# Microcontrolador.net
KiCad netlist of a schematic drawn in Altium Designer
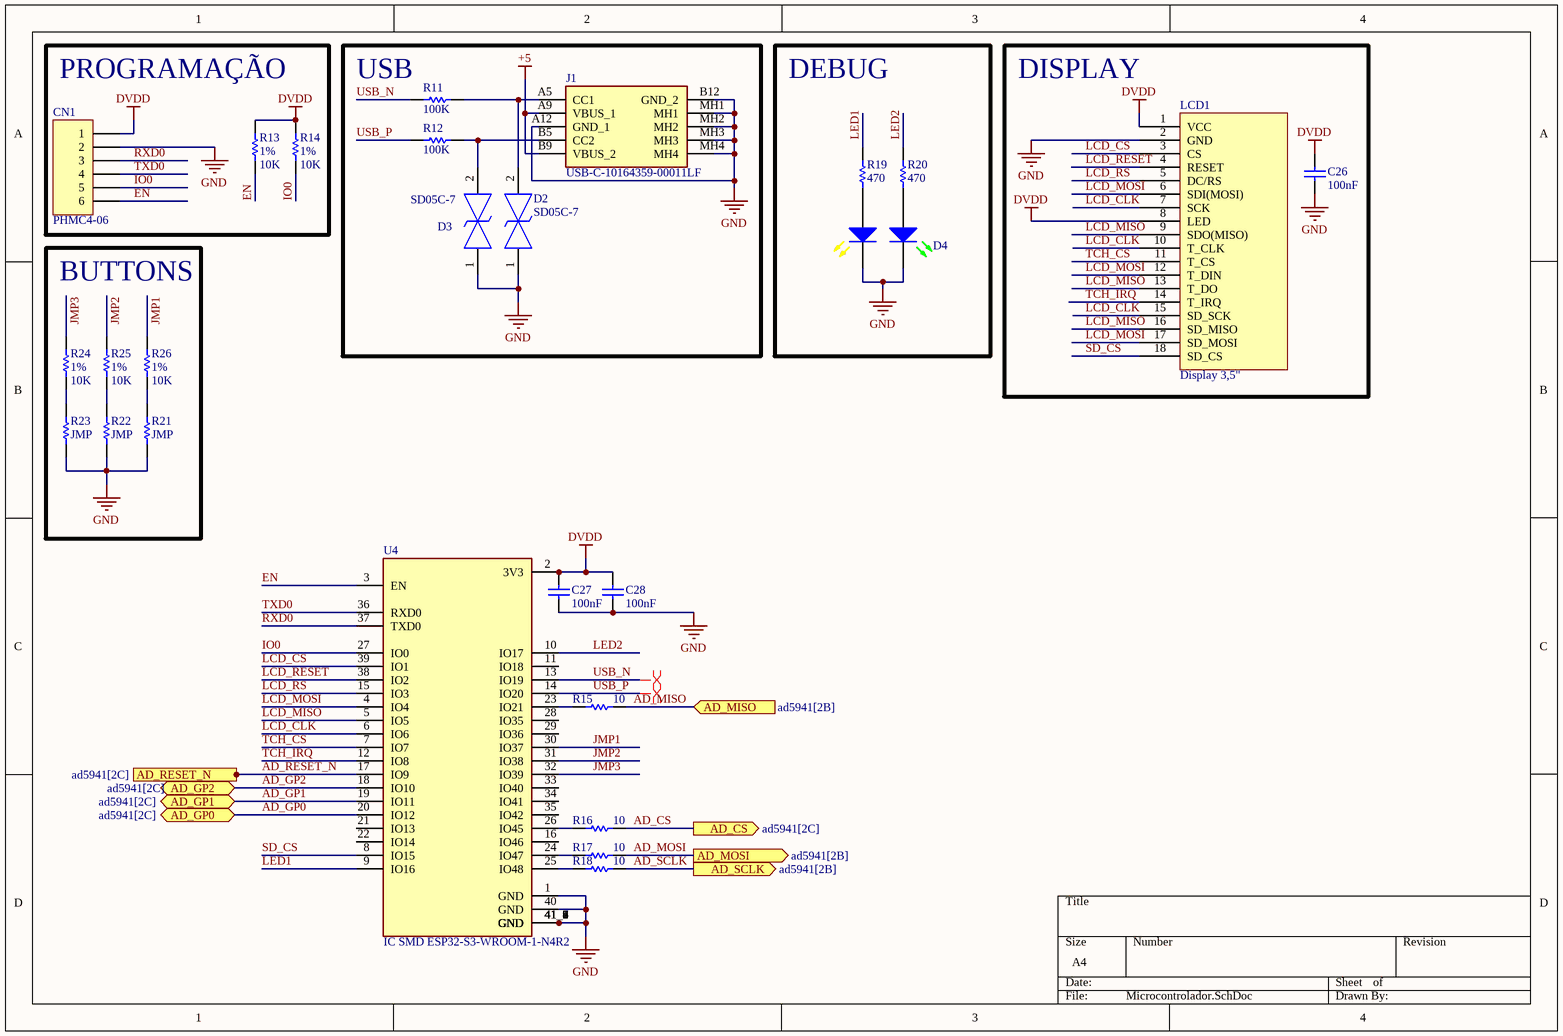
[diagram p0: Microcontrolador.SchDoc]

(export (version "E")
  (design (tool "Eeschema 10.0.6"))
  (components
    (comp (ref "C26")
      (value "100nF")
      (footprint "CAP0805OK")
      (fields
        (field (name "TOLERANCE") "10%")
        (field (name "VOLTAGE") "25V")
        (field (name "Comment") "CAP SMD CER 100NF 25V 0805")
      )
      (libsource (lib "BIB SCH GERAL") (part "CAP SMD CER 100NF 25V 0805"))
    )
    (comp (ref "C27")
      (value "100nF")
      (footprint "CAP0805OK")
      (fields
        (field (name "TOLERANCE") "10%")
        (field (name "VOLTAGE") "25V")
        (field (name "Comment") "CAP SMD CER 100NF 25V 0805")
      )
      (libsource (lib "BIB SCH GERAL") (part "CAP SMD CER 100NF 25V 0805"))
    )
    (comp (ref "C28")
      (value "100nF")
      (footprint "CAP0805OK")
      (fields
        (field (name "TOLERANCE") "10%")
        (field (name "VOLTAGE") "25V")
        (field (name "Comment") "CAP SMD CER 100NF 25V 0805")
      )
      (libsource (lib "BIB SCH GERAL") (part "CAP SMD CER 100NF 25V 0805"))
    )
    (comp (ref "CN1")
      (value "CN MAC 6 VIAS 180º 2.54MM")
      (footprint "PHMC4-06")
      (description "gravação micro")
      (fields (field (name "MANUFACTURER") "METALTEX") (field (name "MANUFACTURER PART NUMBER") "PHMC4-06"))
      (libsource (lib "BIB SCH GERAL") (part "CN MAC 6 VIAS 180º 2.54MM"))
    )
    (comp (ref "D2")
      (value "SD05C-7")
      (footprint "SOD2513X120N")
      (description "TVS Diode (Bi-directional)")
      (fields (field (name "MOUSER PART NUMBER") "621-SD05C-7"))
      (libsource (lib "BIB SCH GERAL") (part "SD05C-7"))
    )
    (comp (ref "D3")
      (value "SD05C-7")
      (footprint "SOD2513X120N")
      (description "TVS Diode (Bi-directional)")
      (fields (field (name "MOUSER PART NUMBER") "621-SD05C-7"))
      (libsource (lib "BIB SCH GERAL") (part "SD05C-7"))
    )
    (comp (ref "D4")
      (value "LED SMD DUAL")
      (footprint "LTST-C197")
      (libsource (lib "BIB SCH GERAL") (part "LED SMD DUAL"))
    )
    (comp (ref "J1")
      (value "USB-C-10164359-00011LF")
      (footprint "LIB_GERAL_V2:USB-C-1016435900011LF")
      (description "Connector")
      (fields
        (field (name "MANUFACTURER_PART_NUMBER") "10164359-00011LF")
        (field (name "MOUSER PART NUMBER") "649-10164359-00011LF")
      )
      (libsource (lib "BIB SCH GERAL") (part "USB-C-10164359-00011LF"))
    )
    (comp (ref "LCD1")
      (value "Display 3,5\"")
      (footprint "Display_3.5\"_SPI_480X320")
      (description "Display TFT SPI 480X320")
      (libsource (lib "BIB SCH GERAL") (part "Display 3,5{dblquote} SPI"))
    )
    (comp (ref "R11")
      (value "100K")
      (footprint "res0805ok")
      (fields (field (name "TOLERANCE") "1%") (field (name "Comment") "RES SMD 100K 1% 0805"))
      (libsource (lib "BIB SCH GERAL") (part "RES SMD 10K 1% 0805"))
    )
    (comp (ref "R12")
      (value "100K")
      (footprint "res0805ok")
      (fields (field (name "TOLERANCE") "1%") (field (name "Comment") "RES SMD 100K 1% 0805"))
      (libsource (lib "BIB SCH GERAL") (part "RES SMD 10K 1% 0805"))
    )
    (comp (ref "R13")
      (value "10K")
      (footprint "res0805ok")
      (fields (field (name "TOLERANCE") "1%") (field (name "Comment") "RES SMD 10K 1% 0805"))
      (libsource (lib "BIB SCH GERAL") (part "RES SMD 10K 1% 0805"))
    )
    (comp (ref "R14")
      (value "10K")
      (footprint "res0805ok")
      (fields (field (name "TOLERANCE") "1%") (field (name "Comment") "RES SMD 10K 1% 0805"))
      (libsource (lib "BIB SCH GERAL") (part "RES SMD 10K 1% 0805"))
    )
    (comp (ref "R15")
      (value "10")
      (footprint "res0805ok")
      (fields (field (name "TOLERANCE") "1%") (field (name "Comment") "RES SMD 10 1% 0805"))
      (libsource (lib "BIB SCH GERAL") (part "RES SMD 10K 1% 0805"))
    )
    (comp (ref "R16")
      (value "10")
      (footprint "res0805ok")
      (fields (field (name "TOLERANCE") "1%") (field (name "Comment") "RES SMD 10 1% 0805"))
      (libsource (lib "BIB SCH GERAL") (part "RES SMD 10K 1% 0805"))
    )
    (comp (ref "R17")
      (value "10")
      (footprint "res0805ok")
      (fields (field (name "TOLERANCE") "1%") (field (name "Comment") "RES SMD 10 1% 0805"))
      (libsource (lib "BIB SCH GERAL") (part "RES SMD 10K 1% 0805"))
    )
    (comp (ref "R18")
      (value "10")
      (footprint "res0805ok")
      (fields (field (name "TOLERANCE") "1%") (field (name "Comment") "RES SMD 10 1% 0805"))
      (libsource (lib "BIB SCH GERAL") (part "RES SMD 10K 1% 0805"))
    )
    (comp (ref "R19")
      (value "470")
      (footprint "res0805ok")
      (fields (field (name "TOLERANCE") "1%") (field (name "Comment") "RES SMD 1K 1% 0805"))
      (libsource (lib "BIB SCH GERAL") (part "RES SMD 1K 1% 0805"))
    )
    (comp (ref "R20")
      (value "470")
      (footprint "res0805ok")
      (fields (field (name "TOLERANCE") "1%") (field (name "Comment") "RES SMD 1K 1% 0805"))
      (libsource (lib "BIB SCH GERAL") (part "RES SMD 1K 1% 0805"))
    )
    (comp (ref "R21")
      (value "JMP")
      (footprint "JMP0805")
      (fields (field (name "TOLERANCE") "1%") (field (name "Comment") "RES SMD 10K 1% 0805"))
      (libsource (lib "BIB SCH GERAL") (part "RES SMD 10K 1% 0805"))
    )
    (comp (ref "R22")
      (value "JMP")
      (footprint "JMP0805")
      (fields (field (name "TOLERANCE") "1%") (field (name "Comment") "RES SMD 10K 1% 0805"))
      (libsource (lib "BIB SCH GERAL") (part "RES SMD 10K 1% 0805"))
    )
    (comp (ref "R23")
      (value "JMP")
      (footprint "JMP0805")
      (fields (field (name "TOLERANCE") "1%") (field (name "Comment") "RES SMD 10K 1% 0805"))
      (libsource (lib "BIB SCH GERAL") (part "RES SMD 10K 1% 0805"))
    )
    (comp (ref "R24")
      (value "10K")
      (footprint "res0805ok")
      (fields (field (name "TOLERANCE") "1%") (field (name "Comment") "RES SMD 10K 1% 0805"))
      (libsource (lib "BIB SCH GERAL") (part "RES SMD 10K 1% 0805"))
    )
    (comp (ref "R25")
      (value "10K")
      (footprint "res0805ok")
      (fields (field (name "TOLERANCE") "1%") (field (name "Comment") "RES SMD 10K 1% 0805"))
      (libsource (lib "BIB SCH GERAL") (part "RES SMD 10K 1% 0805"))
    )
    (comp (ref "R26")
      (value "10K")
      (footprint "res0805ok")
      (fields (field (name "TOLERANCE") "1%") (field (name "Comment") "RES SMD 10K 1% 0805"))
      (libsource (lib "BIB SCH GERAL") (part "RES SMD 10K 1% 0805"))
    )
    (comp (ref "U4")
      (value "IC SMD ESP32-S3-WROOM-1-N4R2")
      (footprint "XCVR_ESP32-S3-WROOM-1-N4R2")
      (description "Bluetooth, WiFi 802.11b/g/n, Bluetooth v5.0 Transceiver Module 2.4GHz PCB Trace Surface Mount")
      (fields (field (name "MF") "Espressif Systems") (field (name "MP") "ESP32-S3-WROOM-1-N4R2"))
      (libsource (lib "BIB SCH GERAL") (part "IC SMD ESP32-S3-WROOM-1-N4R2"))
    )
  )
  (nets
    (net (code "1") (name "+5") (class "Default")
      (node (ref "J1") (pin "A9") (pinfunction "VBUS_1_A9") (pintype "passive"))
      (node (ref "J1") (pin "B9") (pinfunction "VBUS_2_B9") (pintype "passive"))
    )
    (net (code "2") (name "/AD_CS") (class "Default")
      (node (ref "R16") (pin "1") (pinfunction "1_1") (pintype "passive"))
    )
    (net (code "3") (name "/AD_GP0") (class "Default")
      (node (ref "U4") (pin "20") (pinfunction "IO12_20") (pintype "passive"))
    )
    (net (code "4") (name "/AD_GP1") (class "Default")
      (node (ref "U4") (pin "19") (pinfunction "IO11_19") (pintype "passive"))
    )
    (net (code "5") (name "/AD_GP2") (class "Default")
      (node (ref "U4") (pin "18") (pinfunction "IO10_18") (pintype "passive"))
    )
    (net (code "6") (name "/AD_MISO") (class "Default")
      (node (ref "R15") (pin "1") (pinfunction "1_1") (pintype "passive"))
    )
    (net (code "7") (name "/AD_MOSI") (class "Default")
      (node (ref "R17") (pin "1") (pinfunction "1_1") (pintype "passive"))
    )
    (net (code "8") (name "/AD_RESET_N") (class "Default")
      (node (ref "U4") (pin "17") (pinfunction "IO9_17") (pintype "passive"))
    )
    (net (code "9") (name "/AD_SCLK") (class "Default")
      (node (ref "R18") (pin "1") (pinfunction "1_1") (pintype "passive"))
    )
    (net (code "10") (name "/EN") (class "Default")
      (node (ref "CN1") (pin "6") (pinfunction "6_6") (pintype "passive"))
      (node (ref "R13") (pin "1") (pinfunction "1_1") (pintype "passive"))
      (node (ref "U4") (pin "3") (pinfunction "EN_3") (pintype "passive"))
    )
    (net (code "11") (name "/IO0") (class "Default")
      (node (ref "CN1") (pin "5") (pinfunction "5_5") (pintype "passive"))
      (node (ref "R14") (pin "1") (pinfunction "1_1") (pintype "passive"))
      (node (ref "U4") (pin "27") (pinfunction "IO0_27") (pintype "passive"))
    )
    (net (code "12") (name "/JMP1") (class "Default")
      (node (ref "R26") (pin "2") (pinfunction "2_2") (pintype "passive"))
      (node (ref "U4") (pin "30") (pinfunction "IO37_30") (pintype "passive"))
    )
    (net (code "13") (name "/JMP2") (class "Default")
      (node (ref "R25") (pin "2") (pinfunction "2_2") (pintype "passive"))
      (node (ref "U4") (pin "31") (pinfunction "IO38_31") (pintype "passive"))
    )
    (net (code "14") (name "/JMP3") (class "Default")
      (node (ref "R24") (pin "2") (pinfunction "2_2") (pintype "passive"))
      (node (ref "U4") (pin "32") (pinfunction "IO39_32") (pintype "passive"))
    )
    (net (code "15") (name "/LCD_CLK") (class "Default")
      (node (ref "LCD1") (pin "10") (pinfunction "T_CLK_10") (pintype "passive"))
      (node (ref "LCD1") (pin "15") (pinfunction "SD_SCK_15") (pintype "passive"))
      (node (ref "LCD1") (pin "7") (pinfunction "SCK_7") (pintype "passive"))
      (node (ref "U4") (pin "6") (pinfunction "IO6_6") (pintype "passive"))
    )
    (net (code "16") (name "/LCD_CS") (class "Default")
      (node (ref "LCD1") (pin "3") (pinfunction "CS_3") (pintype "passive"))
      (node (ref "U4") (pin "39") (pinfunction "IO1_39") (pintype "passive"))
    )
    (net (code "17") (name "/LCD_MISO") (class "Default")
      (node (ref "LCD1") (pin "13") (pinfunction "T_DO_13") (pintype "passive"))
      (node (ref "LCD1") (pin "16") (pinfunction "SD_MISO_16") (pintype "passive"))
      (node (ref "LCD1") (pin "9") (pinfunction "SDO(MISO)_9") (pintype "passive"))
      (node (ref "U4") (pin "5") (pinfunction "IO5_5") (pintype "passive"))
    )
    (net (code "18") (name "/LCD_MOSI") (class "Default")
      (node (ref "LCD1") (pin "12") (pinfunction "T_DIN_12") (pintype "passive"))
      (node (ref "LCD1") (pin "17") (pinfunction "SD_MOSI_17") (pintype "passive"))
      (node (ref "LCD1") (pin "6") (pinfunction "SDI(MOSI)_6") (pintype "passive"))
      (node (ref "U4") (pin "4") (pinfunction "IO4_4") (pintype "passive"))
    )
    (net (code "19") (name "/LCD_RESET") (class "Default")
      (node (ref "LCD1") (pin "4") (pinfunction "RESET_4") (pintype "passive"))
      (node (ref "U4") (pin "38") (pinfunction "IO2_38") (pintype "passive"))
    )
    (net (code "20") (name "/LCD_RS") (class "Default")
      (node (ref "LCD1") (pin "5") (pinfunction "DC/RS_5") (pintype "passive"))
      (node (ref "U4") (pin "15") (pinfunction "IO3_15") (pintype "passive"))
    )
    (net (code "21") (name "/LED1") (class "Default")
      (node (ref "R19") (pin "2") (pinfunction "2_2") (pintype "passive"))
      (node (ref "U4") (pin "9") (pinfunction "IO16_9") (pintype "passive"))
    )
    (net (code "22") (name "/LED2") (class "Default")
      (node (ref "R20") (pin "2") (pinfunction "2_2") (pintype "passive"))
      (node (ref "U4") (pin "10") (pinfunction "IO17_10") (pintype "passive"))
    )
    (net (code "23") (name "/RXD0") (class "Default")
      (node (ref "CN1") (pin "3") (pinfunction "3_3") (pintype "passive"))
      (node (ref "U4") (pin "37") (pinfunction "TXD0_37") (pintype "passive"))
    )
    (net (code "24") (name "/SD_CS") (class "Default")
      (node (ref "LCD1") (pin "18") (pinfunction "SD_CS_18") (pintype "passive"))
      (node (ref "U4") (pin "8") (pinfunction "IO15_8") (pintype "passive"))
    )
    (net (code "25") (name "/TCH_CS") (class "Default")
      (node (ref "LCD1") (pin "11") (pinfunction "T_CS_11") (pintype "passive"))
      (node (ref "U4") (pin "7") (pinfunction "IO7_7") (pintype "passive"))
    )
    (net (code "26") (name "/TCH_IRQ") (class "Default")
      (node (ref "LCD1") (pin "14") (pinfunction "T_IRQ_14") (pintype "passive"))
      (node (ref "U4") (pin "12") (pinfunction "IO8_12") (pintype "passive"))
    )
    (net (code "27") (name "/TXD0") (class "Default")
      (node (ref "CN1") (pin "4") (pinfunction "4_4") (pintype "passive"))
      (node (ref "U4") (pin "36") (pinfunction "RXD0_36") (pintype "passive"))
    )
    (net (code "28") (name "/USB_N") (class "Default")
      (node (ref "R11") (pin "2") (pinfunction "2_2") (pintype "passive"))
      (node (ref "U4") (pin "13") (pinfunction "IO19_13") (pintype "passive"))
    )
    (net (code "29") (name "/USB_P") (class "Default")
      (node (ref "R12") (pin "2") (pinfunction "2_2") (pintype "passive"))
      (node (ref "U4") (pin "14") (pinfunction "IO20_14") (pintype "passive"))
    )
    (net (code "30") (name "DVDD") (class "Default")
      (node (ref "C26") (pin "2") (pinfunction "2_2") (pintype "passive"))
      (node (ref "C27") (pin "1") (pinfunction "1_1") (pintype "passive"))
      (node (ref "C28") (pin "1") (pinfunction "1_1") (pintype "passive"))
      (node (ref "CN1") (pin "1") (pinfunction "1_1") (pintype "passive"))
      (node (ref "LCD1") (pin "1") (pinfunction "VCC_1") (pintype "power_in"))
      (node (ref "LCD1") (pin "8") (pinfunction "LED_8") (pintype "passive"))
      (node (ref "R13") (pin "2") (pinfunction "2_2") (pintype "passive"))
      (node (ref "R14") (pin "2") (pinfunction "2_2") (pintype "passive"))
      (node (ref "U4") (pin "2") (pinfunction "3V3_2") (pintype "power_in"))
    )
    (net (code "31") (name "GND") (class "Default")
      (node (ref "C26") (pin "1") (pinfunction "1_1") (pintype "passive"))
      (node (ref "C27") (pin "2") (pinfunction "2_2") (pintype "passive"))
      (node (ref "C28") (pin "2") (pinfunction "2_2") (pintype "passive"))
      (node (ref "CN1") (pin "2") (pinfunction "2_2") (pintype "passive"))
      (node (ref "D2") (pin "1") (pinfunction "1_1") (pintype "passive"))
      (node (ref "D3") (pin "1") (pinfunction "1_1") (pintype "passive"))
      (node (ref "D4") (pin "3") (pinfunction "K_3") (pintype "passive"))
      (node (ref "D4") (pin "4") (pinfunction "K_4") (pintype "passive"))
      (node (ref "J1") (pin "A12") (pinfunction "GND_1_A12") (pintype "passive"))
      (node (ref "J1") (pin "B12") (pinfunction "GND_2_B12") (pintype "passive"))
      (node (ref "J1") (pin "MH1") (pinfunction "MH1_MH1") (pintype "passive"))
      (node (ref "J1") (pin "MH2") (pinfunction "MH2_MH2") (pintype "passive"))
      (node (ref "J1") (pin "MH3") (pinfunction "MH3_MH3") (pintype "passive"))
      (node (ref "J1") (pin "MH4") (pinfunction "MH4_MH4") (pintype "passive"))
      (node (ref "LCD1") (pin "2") (pinfunction "GND_2") (pintype "power_in"))
      (node (ref "R21") (pin "2") (pinfunction "2_2") (pintype "passive"))
      (node (ref "R22") (pin "2") (pinfunction "2_2") (pintype "passive"))
      (node (ref "R23") (pin "2") (pinfunction "2_2") (pintype "passive"))
      (node (ref "U4") (pin "1") (pinfunction "GND_1") (pintype "power_in"))
      (node (ref "U4") (pin "40") (pinfunction "GND_40") (pintype "power_in"))
      (node (ref "U4") (pin "41_1") (pinfunction "GND_41_1") (pintype "power_in"))
      (node (ref "U4") (pin "41_2") (pinfunction "GND_41_2") (pintype "power_in"))
      (node (ref "U4") (pin "41_3") (pinfunction "GND_41_3") (pintype "power_in"))
      (node (ref "U4") (pin "41_4") (pinfunction "GND_41_4") (pintype "power_in"))
      (node (ref "U4") (pin "41_5") (pinfunction "GND_41_5") (pintype "power_in"))
      (node (ref "U4") (pin "41_6") (pinfunction "GND_41_6") (pintype "power_in"))
      (node (ref "U4") (pin "41_7") (pinfunction "GND_41_7") (pintype "power_in"))
      (node (ref "U4") (pin "41_8") (pinfunction "GND_41_8") (pintype "power_in"))
      (node (ref "U4") (pin "41_9") (pinfunction "GND_41_9") (pintype "power_in"))
    )
    (net (code "32") (name "Net-(D4-A-Pad1)") (class "Default")
      (node (ref "D4") (pin "1") (pinfunction "A_1") (pintype "passive"))
      (node (ref "R20") (pin "1") (pinfunction "1_1") (pintype "passive"))
    )
    (net (code "33") (name "Net-(D4-A-Pad2)") (class "Default")
      (node (ref "D4") (pin "2") (pinfunction "A_2") (pintype "passive"))
      (node (ref "R19") (pin "1") (pinfunction "1_1") (pintype "passive"))
    )
    (net (code "34") (name "Net-(J1-CC1)") (class "Default")
      (node (ref "D2") (pin "2") (pinfunction "2_2") (pintype "passive"))
      (node (ref "J1") (pin "A5") (pinfunction "CC1_A5") (pintype "passive"))
      (node (ref "R11") (pin "1") (pinfunction "1_1") (pintype "passive"))
    )
    (net (code "35") (name "Net-(J1-CC2)") (class "Default")
      (node (ref "D3") (pin "2") (pinfunction "2_2") (pintype "passive"))
      (node (ref "J1") (pin "B5") (pinfunction "CC2_B5") (pintype "passive"))
      (node (ref "R12") (pin "1") (pinfunction "1_1") (pintype "passive"))
    )
    (net (code "36") (name "Net-(R21-Pad1)") (class "Default")
      (node (ref "R21") (pin "1") (pinfunction "1_1") (pintype "passive"))
      (node (ref "R26") (pin "1") (pinfunction "1_1") (pintype "passive"))
    )
    (net (code "37") (name "Net-(R22-Pad1)") (class "Default")
      (node (ref "R22") (pin "1") (pinfunction "1_1") (pintype "passive"))
      (node (ref "R25") (pin "1") (pinfunction "1_1") (pintype "passive"))
    )
    (net (code "38") (name "Net-(R23-Pad1)") (class "Default")
      (node (ref "R23") (pin "1") (pinfunction "1_1") (pintype "passive"))
      (node (ref "R24") (pin "1") (pinfunction "1_1") (pintype "passive"))
    )
    (net (code "39") (name "Net-(U4-IO21)") (class "Default")
      (node (ref "R15") (pin "2") (pinfunction "2_2") (pintype "passive"))
      (node (ref "U4") (pin "23") (pinfunction "IO21_23") (pintype "passive"))
    )
    (net (code "40") (name "Net-(U4-IO45)") (class "Default")
      (node (ref "R16") (pin "2") (pinfunction "2_2") (pintype "passive"))
      (node (ref "U4") (pin "26") (pinfunction "IO45_26") (pintype "passive"))
    )
    (net (code "41") (name "Net-(U4-IO47)") (class "Default")
      (node (ref "R17") (pin "2") (pinfunction "2_2") (pintype "passive"))
      (node (ref "U4") (pin "24") (pinfunction "IO47_24") (pintype "passive"))
    )
    (net (code "42") (name "Net-(U4-IO48)") (class "Default")
      (node (ref "R18") (pin "2") (pinfunction "2_2") (pintype "passive"))
      (node (ref "U4") (pin "25") (pinfunction "IO48_25") (pintype "passive"))
    )
    (net (code "43") (name "unconnected-(U4-IO13-Pad21)") (class "Default")
      (node (ref "U4") (pin "21") (pinfunction "IO13_21") (pintype "passive"))
    )
    (net (code "44") (name "unconnected-(U4-IO14-Pad22)") (class "Default")
      (node (ref "U4") (pin "22") (pinfunction "IO14_22") (pintype "passive"))
    )
    (net (code "45") (name "unconnected-(U4-IO18-Pad11)") (class "Default")
      (node (ref "U4") (pin "11") (pinfunction "IO18_11") (pintype "passive"))
    )
    (net (code "46") (name "unconnected-(U4-IO35-Pad28)") (class "Default")
      (node (ref "U4") (pin "28") (pinfunction "IO35_28") (pintype "passive"))
    )
    (net (code "47") (name "unconnected-(U4-IO36-Pad29)") (class "Default")
      (node (ref "U4") (pin "29") (pinfunction "IO36_29") (pintype "passive"))
    )
    (net (code "48") (name "unconnected-(U4-IO40-Pad33)") (class "Default")
      (node (ref "U4") (pin "33") (pinfunction "IO40_33") (pintype "passive"))
    )
    (net (code "49") (name "unconnected-(U4-IO41-Pad34)") (class "Default")
      (node (ref "U4") (pin "34") (pinfunction "IO41_34") (pintype "passive"))
    )
    (net (code "50") (name "unconnected-(U4-IO42-Pad35)") (class "Default")
      (node (ref "U4") (pin "35") (pinfunction "IO42_35") (pintype "passive"))
    )
    (net (code "51") (name "unconnected-(U4-IO46-Pad16)") (class "Default")
      (node (ref "U4") (pin "16") (pinfunction "IO46_16") (pintype "passive"))
    )
  )
)
